# ECG_NEMO_final_V1B_main_stack1_fix.net
KiCad netlist of a schematic drawn in Altium Designer
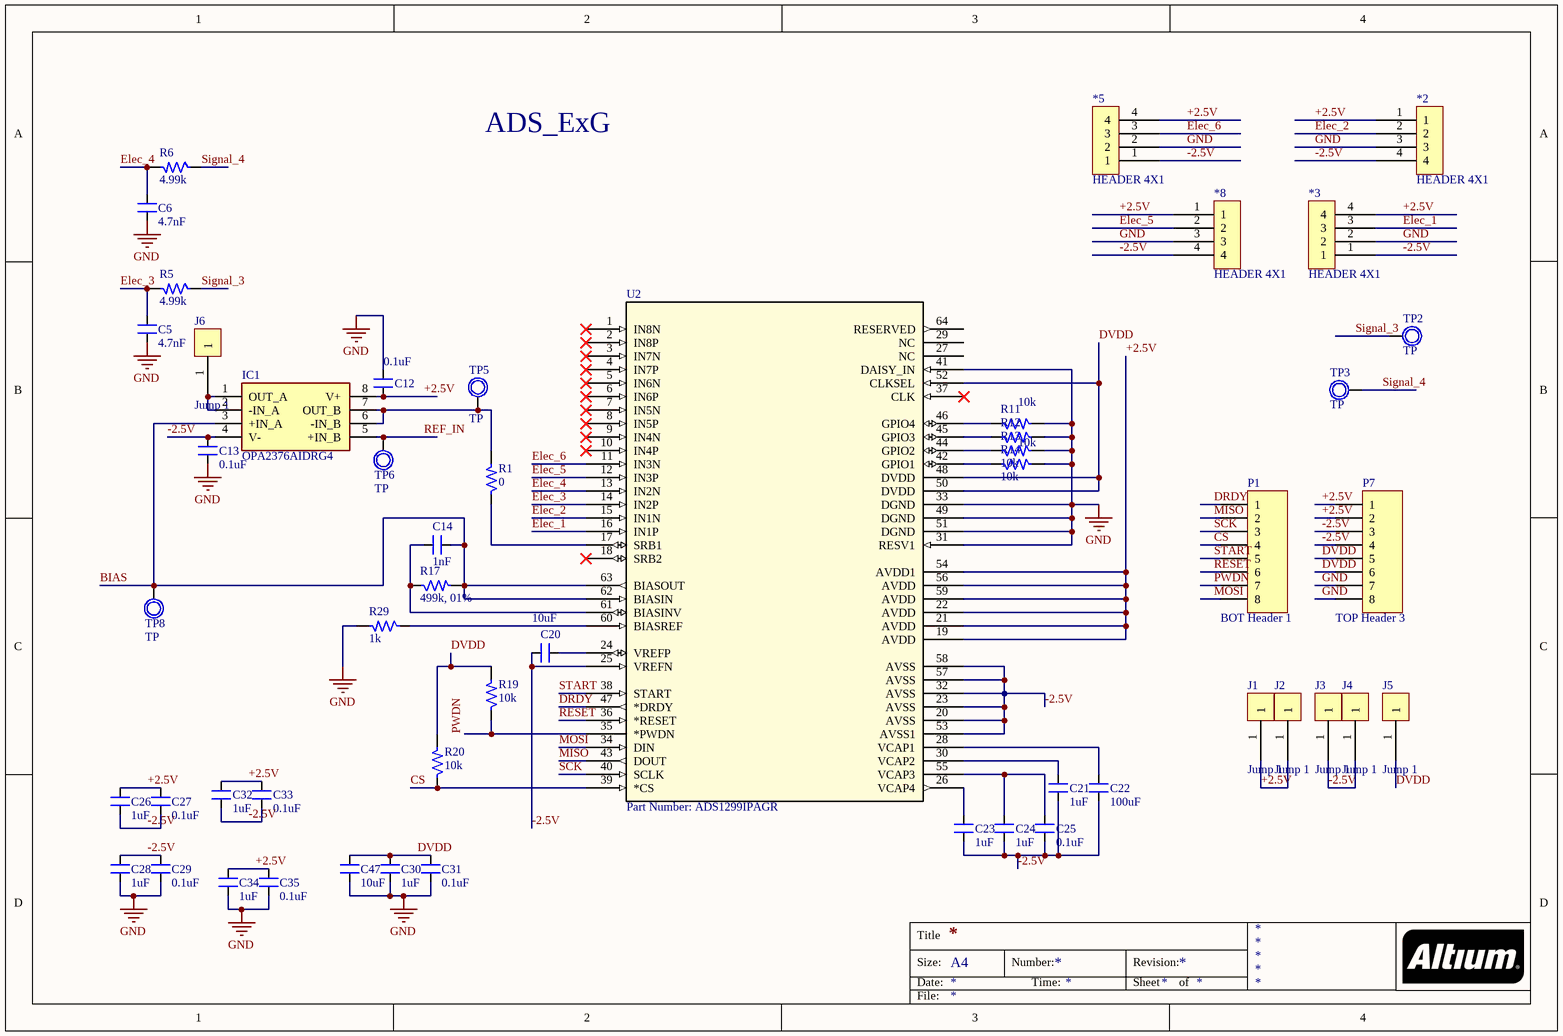
[diagram p0: ECG_NEMO_final_V1B_main_stack1_fix.schdoc]

(export (version "E")
  (design (tool "Eeschema 10.0.6"))
  (components
    (comp (ref "*2")
      (value "HEADER 4X1")
      (footprint "HEADER4X1")
      (libsource (lib "TechMT.VN_Lib_Project v1.0") (part "HEADER 4X1"))
    )
    (comp (ref "*3") (value "HEADER 4X1") (footprint "HEADER4X1") (libsource (lib "") (part "HEADER 4X1_1")))
    (comp (ref "*5") (value "HEADER 4X1") (footprint "HEADER4X1") (libsource (lib "") (part "HEADER 4X1_1")))
    (comp (ref "*8")
      (value "HEADER 4X1")
      (footprint "HEADER4X1")
      (libsource (lib "TechMT.VN_Lib_Project v1.0") (part "HEADER 4X1"))
    )
    (comp (ref "C5")
      (value "4.7nF")
      (footprint "SM-0805")
      (description "Cap SMD")
      (libsource (lib "VioletofSun") (part "CM"))
    )
    (comp (ref "C6")
      (value "4.7nF")
      (footprint "SM-0805")
      (description "Cap SMD")
      (libsource (lib "VioletofSun") (part "CM"))
    )
    (comp (ref "C12")
      (value "0.1uF")
      (footprint "SM-0805")
      (description "Cap SMD")
      (libsource (lib "VioletofSun") (part "CM"))
    )
    (comp (ref "C13")
      (value "0.1uF")
      (footprint "SM-0805")
      (description "Cap SMD")
      (libsource (lib "VioletofSun") (part "CM"))
    )
    (comp (ref "C14")
      (value "1nF")
      (footprint "SM-0805")
      (description "Cap SMD")
      (libsource (lib "VioletofSun") (part "CM"))
    )
    (comp (ref "C20")
      (value "10uF")
      (footprint "SM-0805")
      (description "Cap SMD")
      (libsource (lib "VioletofSun") (part "CM"))
    )
    (comp (ref "C21")
      (value "1uF")
      (footprint "SM-0805")
      (description "Cap SMD")
      (libsource (lib "VioletofSun") (part "CM"))
    )
    (comp (ref "C22")
      (value "100uF")
      (footprint "SM-0805")
      (description "Cap SMD")
      (libsource (lib "VioletofSun") (part "CM"))
    )
    (comp (ref "C23")
      (value "1uF")
      (footprint "SM-0805")
      (description "Cap SMD")
      (libsource (lib "VioletofSun") (part "CM"))
    )
    (comp (ref "C24")
      (value "1uF")
      (footprint "SM-0805")
      (description "Cap SMD")
      (libsource (lib "VioletofSun") (part "CM"))
    )
    (comp (ref "C25")
      (value "0.1uF")
      (footprint "SM-0805")
      (description "Cap SMD")
      (libsource (lib "VioletofSun") (part "CM"))
    )
    (comp (ref "C26")
      (value "1uF")
      (footprint "SM-0805")
      (description "Cap SMD")
      (libsource (lib "VioletofSun") (part "CM"))
    )
    (comp (ref "C27")
      (value "0.1uF")
      (footprint "SM-0805")
      (description "Cap SMD")
      (libsource (lib "VioletofSun") (part "CM"))
    )
    (comp (ref "C28")
      (value "1uF")
      (footprint "SM-0805")
      (description "Cap SMD")
      (libsource (lib "VioletofSun") (part "CM"))
    )
    (comp (ref "C29")
      (value "0.1uF")
      (footprint "SM-0805")
      (description "Cap SMD")
      (libsource (lib "VioletofSun") (part "CM"))
    )
    (comp (ref "C30")
      (value "1uF")
      (footprint "SM-0805")
      (description "Cap SMD")
      (libsource (lib "VioletofSun") (part "CM"))
    )
    (comp (ref "C31")
      (value "0.1uF")
      (footprint "SM-0805")
      (description "Cap SMD")
      (libsource (lib "VioletofSun") (part "CM"))
    )
    (comp (ref "C32")
      (value "1uF")
      (footprint "SM-0805")
      (description "Cap SMD")
      (libsource (lib "VioletofSun") (part "CM"))
    )
    (comp (ref "C33")
      (value "0.1uF")
      (footprint "SM-0805")
      (description "Cap SMD")
      (libsource (lib "VioletofSun") (part "CM"))
    )
    (comp (ref "C34")
      (value "1uF")
      (footprint "SM-0805")
      (description "Cap SMD")
      (libsource (lib "VioletofSun") (part "CM"))
    )
    (comp (ref "C35")
      (value "0.1uF")
      (footprint "SM-0805")
      (description "Cap SMD")
      (libsource (lib "VioletofSun") (part "CM"))
    )
    (comp (ref "C47")
      (value "10uF")
      (footprint "SM-0805")
      (description "Cap SMD")
      (libsource (lib "VioletofSun") (part "CM"))
    )
    (comp (ref "IC1")
      (value "OPA2376AIDRG4")
      (footprint "OPA2376AIDR4:SOIC127P600X175-8N")
      (description "Integrated Circuit")
      (fields (field (name "MOUSER PART NUMBER") "595-OPA2376AIDRG4"))
      (libsource (lib "OPA2376AIDR4") (part "OPA2376AIDRG4"))
    )
    (comp (ref "J1") (value "Jump 1") (footprint "PCBComponent_1") (libsource (lib "jump1") (part "jump1")))
    (comp (ref "J2") (value "Jump 1") (footprint "PCBComponent_1") (libsource (lib "jump1") (part "jump1")))
    (comp (ref "J3") (value "Jump 1") (footprint "PCBComponent_1") (libsource (lib "jump1") (part "jump1")))
    (comp (ref "J4") (value "Jump 1") (footprint "PCBComponent_1") (libsource (lib "jump1") (part "jump1")))
    (comp (ref "J5") (value "Jump 1") (footprint "PCBComponent_1") (libsource (lib "jump1") (part "jump1")))
    (comp (ref "J6") (value "Jump 1") (footprint "PCBComponent_1") (libsource (lib "jump1") (part "jump1")))
    (comp (ref "P1")
      (value "BOT Header 1")
      (footprint "HDR1X8")
      (description "Header, 8-Pin")
      (fields (field (name "PUBLISHER") "Altium Limited"))
      (libsource (lib "Miscellaneous Connectors") (part "Header 8"))
    )
    (comp (ref "P7")
      (value "TOP Header 3")
      (footprint "HDR1X8")
      (description "Header, 8-Pin")
      (fields (field (name "PUBLISHER") "Altium Limited"))
      (libsource (lib "Miscellaneous Connectors") (part "Header 8"))
    )
    (comp (ref "R1")
      (value "0")
      (footprint "SM-0805")
      (description "Resistor 1/4W")
      (libsource (lib "VioletofSun") (part "R"))
    )
    (comp (ref "R5")
      (value "4.99k")
      (footprint "SM-0805")
      (description "Resistor 1/4W")
      (libsource (lib "VioletofSun") (part "R"))
    )
    (comp (ref "R6")
      (value "4.99k")
      (footprint "SM-0805")
      (description "Resistor 1/4W")
      (libsource (lib "VioletofSun") (part "R"))
    )
    (comp (ref "R11")
      (value "10k")
      (footprint "SM-0805")
      (description "Resistor 1/4W")
      (libsource (lib "VioletofSun") (part "R"))
    )
    (comp (ref "R12")
      (value "10k")
      (footprint "SM-0805")
      (description "Resistor 1/4W")
      (libsource (lib "VioletofSun") (part "R"))
    )
    (comp (ref "R13")
      (value "10k")
      (footprint "SM-0805")
      (description "Resistor 1/4W")
      (libsource (lib "VioletofSun") (part "R"))
    )
    (comp (ref "R14")
      (value "10k")
      (footprint "SM-0805")
      (description "Resistor 1/4W")
      (libsource (lib "VioletofSun") (part "R"))
    )
    (comp (ref "R17")
      (value "499k, 01%")
      (footprint "SM-0805")
      (description "Resistor 1/4W")
      (libsource (lib "VioletofSun") (part "R"))
    )
    (comp (ref "R19")
      (value "10k")
      (footprint "SM-0805")
      (description "Resistor 1/4W")
      (libsource (lib "VioletofSun") (part "R"))
    )
    (comp (ref "R20")
      (value "10k")
      (footprint "SM-0805")
      (description "Resistor 1/4W")
      (libsource (lib "VioletofSun") (part "R"))
    )
    (comp (ref "R29")
      (value "1k")
      (footprint "SM-0805")
      (description "Resistor 1/4W")
      (libsource (lib "VioletofSun") (part "R"))
    )
    (comp (ref "TP2")
      (value "TP")
      (footprint "TP1")
      (description "Test Point")
      (libsource (lib "") (part "TP1_1"))
    )
    (comp (ref "TP3")
      (value "TP")
      (footprint "TP1")
      (description "Test Point")
      (libsource (lib "syhaunguyen") (part "TP1"))
    )
    (comp (ref "TP5")
      (value "TP")
      (footprint "TP1")
      (description "Test Point")
      (libsource (lib "VioletofSun") (part "TP1"))
    )
    (comp (ref "TP6")
      (value "TP")
      (footprint "TP1")
      (description "Test Point")
      (libsource (lib "") (part "TP1_1"))
    )
    (comp (ref "TP8")
      (value "TP")
      (footprint "TP1")
      (description "Test Point")
      (libsource (lib "") (part "TP1_1"))
    )
    (comp (ref "U2")
      (value "Part Number: ADS1299IPAGR")
      (footprint "QFP50P1200X1200X120-64N")
      (description "No Description Available")
      (fields
        (field (name "MANUFACTURER_PART_NUMBER") "ADS1299IPAGR")
        (field (name "COPYRIGHT") "Copyright (C) 2018 Accelerated Designs. All rights reserved")
      )
      (libsource (lib "Flex-PCB-fmECG") (part "ADS1299IPAGR"))
    )
  )
  (nets
    (net (code "1") (name "/+2.5V") (class "Default")
      (node (ref "*2") (pin "1") (pinfunction "1_1") (pintype "passive"))
      (node (ref "*3") (pin "4") (pinfunction "4_4") (pintype "passive"))
      (node (ref "*5") (pin "4") (pinfunction "4_4") (pintype "passive"))
      (node (ref "*8") (pin "1") (pinfunction "1_1") (pintype "passive"))
      (node (ref "C12") (pin "1") (pinfunction "1_1") (pintype "passive"))
      (node (ref "C26") (pin "2") (pinfunction "2_2") (pintype "passive"))
      (node (ref "C27") (pin "2") (pinfunction "2_2") (pintype "passive"))
      (node (ref "C32") (pin "2") (pinfunction "2_2") (pintype "passive"))
      (node (ref "C33") (pin "2") (pinfunction "2_2") (pintype "passive"))
      (node (ref "C34") (pin "2") (pinfunction "2_2") (pintype "passive"))
      (node (ref "C35") (pin "2") (pinfunction "2_2") (pintype "passive"))
      (node (ref "IC1") (pin "8") (pinfunction "V+_8") (pintype "passive"))
      (node (ref "J1") (pin "1") (pinfunction "1_1") (pintype "passive"))
      (node (ref "J2") (pin "1") (pinfunction "1_1") (pintype "passive"))
      (node (ref "P7") (pin "1") (pinfunction "1_1") (pintype "passive"))
      (node (ref "P7") (pin "2") (pinfunction "2_2") (pintype "passive"))
      (node (ref "U2") (pin "19") (pinfunction "AVDD_19") (pintype "power_in"))
      (node (ref "U2") (pin "21") (pinfunction "AVDD_21") (pintype "power_in"))
      (node (ref "U2") (pin "22") (pinfunction "AVDD_22") (pintype "power_in"))
      (node (ref "U2") (pin "54") (pinfunction "AVDD1_54") (pintype "power_in"))
      (node (ref "U2") (pin "56") (pinfunction "AVDD_56") (pintype "power_in"))
      (node (ref "U2") (pin "59") (pinfunction "AVDD_59") (pintype "power_in"))
    )
    (net (code "2") (name "/-2.5V") (class "Default")
      (node (ref "*2") (pin "4") (pinfunction "4_4") (pintype "passive"))
      (node (ref "*3") (pin "1") (pinfunction "1_1") (pintype "passive"))
      (node (ref "*5") (pin "1") (pinfunction "1_1") (pintype "passive"))
      (node (ref "*8") (pin "4") (pinfunction "4_4") (pintype "passive"))
      (node (ref "C13") (pin "2") (pinfunction "2_2") (pintype "passive"))
      (node (ref "C20") (pin "2") (pinfunction "2_2") (pintype "passive"))
      (node (ref "C21") (pin "1") (pinfunction "1_1") (pintype "passive"))
      (node (ref "C22") (pin "2") (pinfunction "2_2") (pintype "passive"))
      (node (ref "C23") (pin "1") (pinfunction "1_1") (pintype "passive"))
      (node (ref "C24") (pin "1") (pinfunction "1_1") (pintype "passive"))
      (node (ref "C25") (pin "1") (pinfunction "1_1") (pintype "passive"))
      (node (ref "C26") (pin "1") (pinfunction "1_1") (pintype "passive"))
      (node (ref "C27") (pin "1") (pinfunction "1_1") (pintype "passive"))
      (node (ref "C28") (pin "2") (pinfunction "2_2") (pintype "passive"))
      (node (ref "C29") (pin "2") (pinfunction "2_2") (pintype "passive"))
      (node (ref "C32") (pin "1") (pinfunction "1_1") (pintype "passive"))
      (node (ref "C33") (pin "1") (pinfunction "1_1") (pintype "passive"))
      (node (ref "IC1") (pin "4") (pinfunction "V-_4") (pintype "passive"))
      (node (ref "J3") (pin "1") (pinfunction "1_1") (pintype "passive"))
      (node (ref "J4") (pin "1") (pinfunction "1_1") (pintype "passive"))
      (node (ref "P7") (pin "3") (pinfunction "3_3") (pintype "passive"))
      (node (ref "P7") (pin "4") (pinfunction "4_4") (pintype "passive"))
      (node (ref "U2") (pin "20") (pinfunction "AVSS_20") (pintype "power_in"))
      (node (ref "U2") (pin "23") (pinfunction "AVSS_23") (pintype "power_in"))
      (node (ref "U2") (pin "25") (pinfunction "VREFN_25") (pintype "input"))
      (node (ref "U2") (pin "32") (pinfunction "AVSS_32") (pintype "power_in"))
      (node (ref "U2") (pin "53") (pinfunction "AVSS1_53") (pintype "power_in"))
      (node (ref "U2") (pin "57") (pinfunction "AVSS_57") (pintype "power_in"))
      (node (ref "U2") (pin "58") (pinfunction "AVSS_58") (pintype "power_in"))
    )
    (net (code "3") (name "/BIAS") (class "Default")
      (node (ref "C14") (pin "2") (pinfunction "2_2") (pintype "passive"))
      (node (ref "IC1") (pin "3") (pinfunction "+IN_A_3") (pintype "passive"))
      (node (ref "R17") (pin "2") (pinfunction "2_2") (pintype "passive"))
      (node (ref "TP8") (pin "1") (pinfunction "1_1") (pintype "passive"))
      (node (ref "U2") (pin "62") (pinfunction "BIASIN_62") (pintype "input"))
      (node (ref "U2") (pin "63") (pinfunction "BIASOUT_63") (pintype "output"))
    )
    (net (code "4") (name "/CS") (class "Default")
      (node (ref "P1") (pin "4") (pinfunction "4_4") (pintype "passive"))
      (node (ref "R20") (pin "1") (pinfunction "1_1") (pintype "passive"))
      (node (ref "U2") (pin "39") (pinfunction "*CS_39") (pintype "input"))
    )
    (net (code "5") (name "/DRDY") (class "Default")
      (node (ref "P1") (pin "1") (pinfunction "1_1") (pintype "passive"))
      (node (ref "U2") (pin "47") (pinfunction "*DRDY_47") (pintype "output"))
    )
    (net (code "6") (name "/DVDD") (class "Default")
      (node (ref "C30") (pin "2") (pinfunction "2_2") (pintype "passive"))
      (node (ref "C31") (pin "2") (pinfunction "2_2") (pintype "passive"))
      (node (ref "C47") (pin "2") (pinfunction "2_2") (pintype "passive"))
      (node (ref "J5") (pin "1") (pinfunction "1_1") (pintype "passive"))
      (node (ref "P7") (pin "5") (pinfunction "5_5") (pintype "passive"))
      (node (ref "P7") (pin "6") (pinfunction "6_6") (pintype "passive"))
      (node (ref "R19") (pin "2") (pinfunction "2_2") (pintype "passive"))
      (node (ref "R20") (pin "2") (pinfunction "2_2") (pintype "passive"))
      (node (ref "U2") (pin "48") (pinfunction "DVDD_48") (pintype "power_in"))
      (node (ref "U2") (pin "50") (pinfunction "DVDD_50") (pintype "power_in"))
      (node (ref "U2") (pin "52") (pinfunction "CLKSEL_52") (pintype "input"))
    )
    (net (code "7") (name "/Elec_1") (class "Default")
      (node (ref "*3") (pin "3") (pinfunction "3_3") (pintype "passive"))
      (node (ref "U2") (pin "16") (pinfunction "IN1P_16") (pintype "input"))
    )
    (net (code "8") (name "/Elec_2") (class "Default")
      (node (ref "*2") (pin "2") (pinfunction "2_2") (pintype "passive"))
      (node (ref "U2") (pin "15") (pinfunction "IN1N_15") (pintype "input"))
    )
    (net (code "9") (name "/Elec_3") (class "Default")
      (node (ref "C5") (pin "2") (pinfunction "2_2") (pintype "passive"))
      (node (ref "R5") (pin "2") (pinfunction "2_2") (pintype "passive"))
      (node (ref "U2") (pin "14") (pinfunction "IN2P_14") (pintype "input"))
    )
    (net (code "10") (name "/Elec_4") (class "Default")
      (node (ref "C6") (pin "2") (pinfunction "2_2") (pintype "passive"))
      (node (ref "R6") (pin "2") (pinfunction "2_2") (pintype "passive"))
      (node (ref "U2") (pin "13") (pinfunction "IN2N_13") (pintype "input"))
    )
    (net (code "11") (name "/Elec_5") (class "Default")
      (node (ref "*8") (pin "2") (pinfunction "2_2") (pintype "passive"))
      (node (ref "U2") (pin "12") (pinfunction "IN3P_12") (pintype "input"))
    )
    (net (code "12") (name "/Elec_6") (class "Default")
      (node (ref "*5") (pin "3") (pinfunction "3_3") (pintype "passive"))
      (node (ref "U2") (pin "11") (pinfunction "IN3N_11") (pintype "input"))
    )
    (net (code "13") (name "/MISO") (class "Default")
      (node (ref "P1") (pin "2") (pinfunction "2_2") (pintype "passive"))
      (node (ref "U2") (pin "43") (pinfunction "DOUT_43") (pintype "output"))
    )
    (net (code "14") (name "/MOSI") (class "Default")
      (node (ref "P1") (pin "8") (pinfunction "8_8") (pintype "passive"))
      (node (ref "U2") (pin "34") (pinfunction "DIN_34") (pintype "input"))
    )
    (net (code "15") (name "/PWDN") (class "Default")
      (node (ref "P1") (pin "7") (pinfunction "7_7") (pintype "passive"))
      (node (ref "R19") (pin "1") (pinfunction "1_1") (pintype "passive"))
      (node (ref "U2") (pin "35") (pinfunction "*PWDN_35") (pintype "power_in"))
    )
    (net (code "16") (name "/REF_IN") (class "Default")
      (node (ref "IC1") (pin "5") (pinfunction "+IN_B_5") (pintype "passive"))
      (node (ref "TP6") (pin "1") (pinfunction "1_1") (pintype "passive"))
    )
    (net (code "17") (name "/RESET") (class "Default")
      (node (ref "P1") (pin "6") (pinfunction "6_6") (pintype "passive"))
      (node (ref "U2") (pin "36") (pinfunction "*RESET_36") (pintype "input"))
    )
    (net (code "18") (name "/SCK") (class "Default")
      (node (ref "P1") (pin "3") (pinfunction "3_3") (pintype "passive"))
      (node (ref "U2") (pin "40") (pinfunction "SCLK_40") (pintype "input"))
    )
    (net (code "19") (name "/START") (class "Default")
      (node (ref "P1") (pin "5") (pinfunction "5_5") (pintype "passive"))
      (node (ref "U2") (pin "38") (pinfunction "START_38") (pintype "input"))
    )
    (net (code "20") (name "/Signal_3") (class "Default")
      (node (ref "R5") (pin "1") (pinfunction "1_1") (pintype "passive"))
      (node (ref "TP2") (pin "1") (pinfunction "1_1") (pintype "passive"))
    )
    (net (code "21") (name "/Signal_4") (class "Default")
      (node (ref "R6") (pin "1") (pinfunction "1_1") (pintype "passive"))
      (node (ref "TP3") (pin "1") (pinfunction "1_1") (pintype "passive"))
    )
    (net (code "22") (name "GND") (class "Default")
      (node (ref "*2") (pin "3") (pinfunction "3_3") (pintype "passive"))
      (node (ref "*3") (pin "2") (pinfunction "2_2") (pintype "passive"))
      (node (ref "*5") (pin "2") (pinfunction "2_2") (pintype "passive"))
      (node (ref "*8") (pin "3") (pinfunction "3_3") (pintype "passive"))
      (node (ref "C12") (pin "2") (pinfunction "2_2") (pintype "passive"))
      (node (ref "C13") (pin "1") (pinfunction "1_1") (pintype "passive"))
      (node (ref "C28") (pin "1") (pinfunction "1_1") (pintype "passive"))
      (node (ref "C29") (pin "1") (pinfunction "1_1") (pintype "passive"))
      (node (ref "C30") (pin "1") (pinfunction "1_1") (pintype "passive"))
      (node (ref "C31") (pin "1") (pinfunction "1_1") (pintype "passive"))
      (node (ref "C34") (pin "1") (pinfunction "1_1") (pintype "passive"))
      (node (ref "C35") (pin "1") (pinfunction "1_1") (pintype "passive"))
      (node (ref "C47") (pin "1") (pinfunction "1_1") (pintype "passive"))
      (node (ref "C5") (pin "1") (pinfunction "1_1") (pintype "passive"))
      (node (ref "C6") (pin "1") (pinfunction "1_1") (pintype "passive"))
      (node (ref "P7") (pin "7") (pinfunction "7_7") (pintype "passive"))
      (node (ref "P7") (pin "8") (pinfunction "8_8") (pintype "passive"))
      (node (ref "R11") (pin "2") (pinfunction "2_2") (pintype "passive"))
      (node (ref "R12") (pin "2") (pinfunction "2_2") (pintype "passive"))
      (node (ref "R13") (pin "2") (pinfunction "2_2") (pintype "passive"))
      (node (ref "R14") (pin "2") (pinfunction "2_2") (pintype "passive"))
      (node (ref "R29") (pin "2") (pinfunction "2_2") (pintype "passive"))
      (node (ref "U2") (pin "31") (pinfunction "RESV1_31") (pintype "input"))
      (node (ref "U2") (pin "33") (pinfunction "DGND_33") (pintype "power_in"))
      (node (ref "U2") (pin "41") (pinfunction "DAISY_IN_41") (pintype "input"))
      (node (ref "U2") (pin "49") (pinfunction "DGND_49") (pintype "power_in"))
      (node (ref "U2") (pin "51") (pinfunction "DGND_51") (pintype "power_in"))
    )
    (net (code "23") (name "Net-(IC1--IN_A)") (class "Default")
      (node (ref "IC1") (pin "1") (pinfunction "OUT_A_1") (pintype "passive"))
      (node (ref "IC1") (pin "2") (pinfunction "-IN_A_2") (pintype "passive"))
      (node (ref "J6") (pin "1") (pinfunction "1_1") (pintype "passive"))
    )
    (net (code "24") (name "Net-(IC1--IN_B)") (class "Default")
      (node (ref "IC1") (pin "6") (pinfunction "-IN_B_6") (pintype "passive"))
      (node (ref "IC1") (pin "7") (pinfunction "OUT_B_7") (pintype "passive"))
      (node (ref "R1") (pin "2") (pinfunction "2_2") (pintype "passive"))
      (node (ref "TP5") (pin "1") (pinfunction "1_1") (pintype "passive"))
    )
    (net (code "25") (name "Net-(U2-BIASINV)") (class "Default")
      (node (ref "C14") (pin "1") (pinfunction "1_1") (pintype "passive"))
      (node (ref "R17") (pin "1") (pinfunction "1_1") (pintype "passive"))
      (node (ref "U2") (pin "61") (pinfunction "BIASINV_61") (pintype "bidirectional"))
    )
    (net (code "26") (name "Net-(U2-BIASREF)") (class "Default")
      (node (ref "R29") (pin "1") (pinfunction "1_1") (pintype "passive"))
      (node (ref "U2") (pin "60") (pinfunction "BIASREF_60") (pintype "input"))
    )
    (net (code "27") (name "Net-(U2-GPIO1)") (class "Default")
      (node (ref "R14") (pin "1") (pinfunction "1_1") (pintype "passive"))
      (node (ref "U2") (pin "42") (pinfunction "GPIO1_42") (pintype "bidirectional"))
    )
    (net (code "28") (name "Net-(U2-GPIO2)") (class "Default")
      (node (ref "R13") (pin "1") (pinfunction "1_1") (pintype "passive"))
      (node (ref "U2") (pin "44") (pinfunction "GPIO2_44") (pintype "bidirectional"))
    )
    (net (code "29") (name "Net-(U2-GPIO3)") (class "Default")
      (node (ref "R12") (pin "1") (pinfunction "1_1") (pintype "passive"))
      (node (ref "U2") (pin "45") (pinfunction "GPIO3_45") (pintype "bidirectional"))
    )
    (net (code "30") (name "Net-(U2-GPIO4)") (class "Default")
      (node (ref "R11") (pin "1") (pinfunction "1_1") (pintype "passive"))
      (node (ref "U2") (pin "46") (pinfunction "GPIO4_46") (pintype "bidirectional"))
    )
    (net (code "31") (name "Net-(U2-SRB1)") (class "Default")
      (node (ref "R1") (pin "1") (pinfunction "1_1") (pintype "passive"))
      (node (ref "U2") (pin "17") (pinfunction "SRB1_17") (pintype "bidirectional"))
    )
    (net (code "32") (name "Net-(U2-VCAP1)") (class "Default")
      (node (ref "C22") (pin "1") (pinfunction "1_1") (pintype "passive"))
      (node (ref "U2") (pin "28") (pinfunction "VCAP1_28") (pintype "passive"))
    )
    (net (code "33") (name "Net-(U2-VCAP2)") (class "Default")
      (node (ref "C21") (pin "2") (pinfunction "2_2") (pintype "passive"))
      (node (ref "U2") (pin "30") (pinfunction "VCAP2_30") (pintype "passive"))
    )
    (net (code "34") (name "Net-(U2-VCAP3)") (class "Default")
      (node (ref "C24") (pin "2") (pinfunction "2_2") (pintype "passive"))
      (node (ref "C25") (pin "2") (pinfunction "2_2") (pintype "passive"))
      (node (ref "U2") (pin "55") (pinfunction "VCAP3_55") (pintype "passive"))
    )
    (net (code "35") (name "Net-(U2-VCAP4)") (class "Default")
      (node (ref "C23") (pin "2") (pinfunction "2_2") (pintype "passive"))
      (node (ref "U2") (pin "26") (pinfunction "VCAP4_26") (pintype "output"))
    )
    (net (code "36") (name "Net-(U2-VREFP)") (class "Default")
      (node (ref "C20") (pin "1") (pinfunction "1_1") (pintype "passive"))
      (node (ref "U2") (pin "24") (pinfunction "VREFP_24") (pintype "bidirectional"))
    )
    (net (code "37") (name "unconnected-(U2-CLK-Pad37)") (class "Default")
      (node (ref "U2") (pin "37") (pinfunction "CLK_37") (pintype "input+no_connect"))
    )
    (net (code "38") (name "unconnected-(U2-IN4N-Pad9)") (class "Default")
      (node (ref "U2") (pin "9") (pinfunction "IN4N_9") (pintype "input+no_connect"))
    )
    (net (code "39") (name "unconnected-(U2-IN4P-Pad10)") (class "Default")
      (node (ref "U2") (pin "10") (pinfunction "IN4P_10") (pintype "input+no_connect"))
    )
    (net (code "40") (name "unconnected-(U2-IN5N-Pad7)") (class "Default")
      (node (ref "U2") (pin "7") (pinfunction "IN5N_7") (pintype "input+no_connect"))
    )
    (net (code "41") (name "unconnected-(U2-IN5P-Pad8)") (class "Default")
      (node (ref "U2") (pin "8") (pinfunction "IN5P_8") (pintype "input+no_connect"))
    )
    (net (code "42") (name "unconnected-(U2-IN6N-Pad5)") (class "Default")
      (node (ref "U2") (pin "5") (pinfunction "IN6N_5") (pintype "input+no_connect"))
    )
    (net (code "43") (name "unconnected-(U2-IN6P-Pad6)") (class "Default")
      (node (ref "U2") (pin "6") (pinfunction "IN6P_6") (pintype "input+no_connect"))
    )
    (net (code "44") (name "unconnected-(U2-IN7N-Pad3)") (class "Default")
      (node (ref "U2") (pin "3") (pinfunction "IN7N_3") (pintype "input+no_connect"))
    )
    (net (code "45") (name "unconnected-(U2-IN7P-Pad4)") (class "Default")
      (node (ref "U2") (pin "4") (pinfunction "IN7P_4") (pintype "input+no_connect"))
    )
    (net (code "46") (name "unconnected-(U2-IN8N-Pad1)") (class "Default")
      (node (ref "U2") (pin "1") (pinfunction "IN8N_1") (pintype "input+no_connect"))
    )
    (net (code "47") (name "unconnected-(U2-IN8P-Pad2)") (class "Default")
      (node (ref "U2") (pin "2") (pinfunction "IN8P_2") (pintype "input+no_connect"))
    )
    (net (code "48") (name "unconnected-(U2-NC-Pad27)") (class "Default")
      (node (ref "U2") (pin "27") (pinfunction "NC_27") (pintype "passive"))
    )
    (net (code "49") (name "unconnected-(U2-NC-Pad29)") (class "Default")
      (node (ref "U2") (pin "29") (pinfunction "NC_29") (pintype "passive"))
    )
    (net (code "50") (name "unconnected-(U2-RESERVED-Pad64)") (class "Default")
      (node (ref "U2") (pin "64") (pinfunction "RESERVED_64") (pintype "output"))
    )
    (net (code "51") (name "unconnected-(U2-SRB2-Pad18)") (class "Default")
      (node (ref "U2") (pin "18") (pinfunction "SRB2_18") (pintype "bidirectional+no_connect"))
    )
  )
)
